# LED.net
KiCad netlist of a schematic drawn in Altium Designer
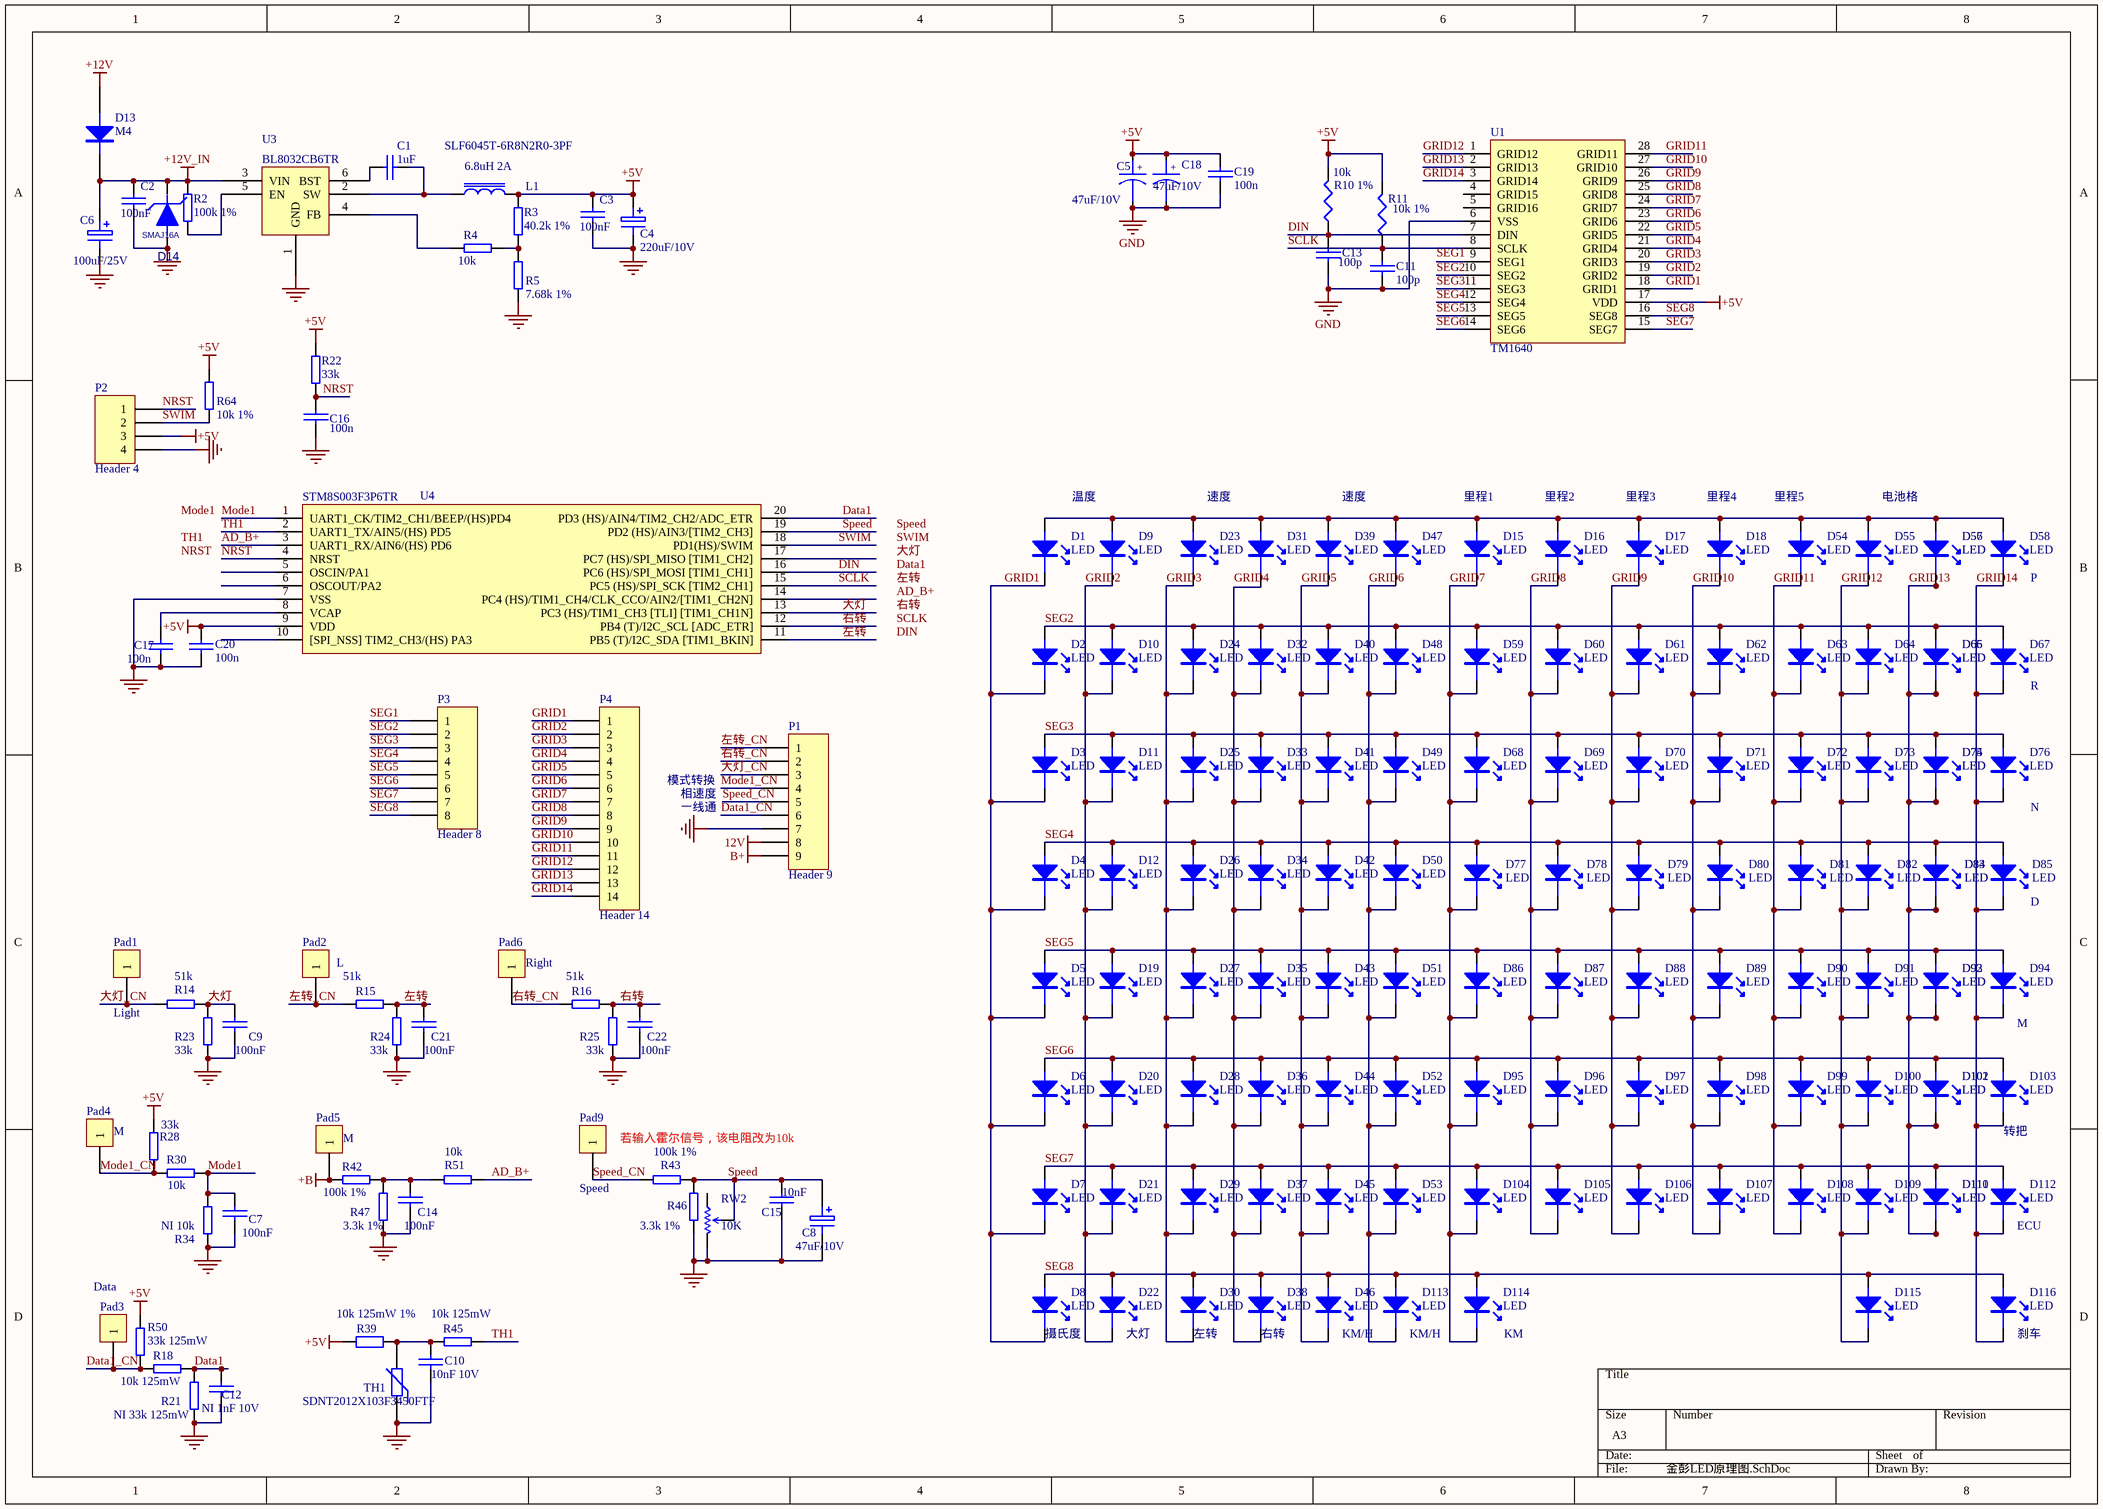
[diagram p0: 金彭LED原理图.SchDoc]

(export (version "E")
  (design (tool "Eeschema 10.0.6"))
  (components
    (comp (ref "C1") (value "1uF") (footprint "0805") (libsource (lib "whlSCHLIB") (part "WHLCAP")))
    (comp (ref "C2")
      (value "100nF")
      (footprint "0805")
      (description "Capacitor")
      (libsource (lib "*") (part "CAP"))
    )
    (comp (ref "C3")
      (value "100nF")
      (footprint "0805")
      (description "Capacitor")
      (libsource (lib "*") (part "CAP"))
    )
    (comp (ref "C4")
      (value "220uF/10V")
      (footprint "CE-D6.4")
      (description "Electrolytic Capacitor")
      (libsource (lib "*") (part "ELECTRO1"))
    )
    (comp (ref "C5") (value "47uF/10V") (footprint "CE-D5.2") (libsource (lib "dsp") (part "Capacitor")))
    (comp (ref "C6")
      (value "100uF/25V")
      (footprint "RB.2/.4")
      (description "Electrolytic Capacitor")
      (libsource (lib "*") (part "ELECTRO1"))
    )
    (comp (ref "C7")
      (value "100nF")
      (footprint "0805")
      (description "Capacitor")
      (libsource (lib "*") (part "CAP"))
    )
    (comp (ref "C8")
      (value "47uF/10V")
      (footprint "RB.1/.2")
      (description "Electrolytic Capacitor")
      (libsource (lib "") (part "ELECTRO1_1"))
    )
    (comp (ref "C9")
      (value "100nF")
      (footprint "0805")
      (description "Capacitor")
      (libsource (lib "*") (part "CAP"))
    )
    (comp (ref "C10")
      (value "10nF 10V")
      (footprint "0603")
      (description "Capacitor")
      (libsource (lib "*") (part "CAP"))
    )
    (comp (ref "C11") (value "100p") (footprint "0805") (libsource (lib "dsp") (part "Cap")))
    (comp (ref "C12")
      (value "NI 1nF 10V")
      (footprint "0603")
      (description "Capacitor")
      (libsource (lib "*") (part "CAP"))
    )
    (comp (ref "C13") (value "100p") (footprint "0805") (libsource (lib "dsp") (part "Cap")))
    (comp (ref "C14")
      (value "100nF")
      (footprint "0805")
      (description "Capacitor")
      (libsource (lib "*") (part "CAP"))
    )
    (comp (ref "C15")
      (value "10nF")
      (footprint "0603")
      (description "Capacitor")
      (libsource (lib "*") (part "CAP"))
    )
    (comp (ref "C16") (value "100n") (footprint "0603") (libsource (lib "dsp") (part "Cap")))
    (comp (ref "C17")
      (value "100n")
      (footprint "0603")
      (description "Capacitor")
      (libsource (lib "*") (part "CAP"))
    )
    (comp (ref "C18") (value "47uF/10V") (footprint "CE-D5.2") (libsource (lib "dsp") (part "Capacitor")))
    (comp (ref "C19") (value "100n") (footprint "0603") (libsource (lib "dsp") (part "Cap")))
    (comp (ref "C20") (value "100n") (footprint "0603") (libsource (lib "dsp") (part "Cap")))
    (comp (ref "C21")
      (value "100nF")
      (footprint "0805")
      (description "Capacitor")
      (libsource (lib "*") (part "CAP"))
    )
    (comp (ref "C22")
      (value "100nF")
      (footprint "0805")
      (description "Capacitor")
      (libsource (lib "*") (part "CAP"))
    )
    (comp (ref "D1") (value "LED") (footprint "0603") (libsource (lib "dsp") (part "LED")))
    (comp (ref "D2") (value "LED") (footprint "0603") (libsource (lib "dsp") (part "LED")))
    (comp (ref "D3") (value "LED") (footprint "0603") (libsource (lib "dsp") (part "LED")))
    (comp (ref "D4") (value "LED") (footprint "0603") (libsource (lib "dsp") (part "LED")))
    (comp (ref "D5") (value "LED") (footprint "0603") (libsource (lib "dsp") (part "LED")))
    (comp (ref "D6") (value "LED") (footprint "0603") (libsource (lib "dsp") (part "LED")))
    (comp (ref "D7") (value "LED") (footprint "0603") (libsource (lib "dsp") (part "LED")))
    (comp (ref "D8") (value "LED") (footprint "0603") (libsource (lib "dsp") (part "LED")))
    (comp (ref "D9") (value "LED") (footprint "0603") (libsource (lib "dsp") (part "LED")))
    (comp (ref "D10") (value "LED") (footprint "0603") (libsource (lib "dsp") (part "LED")))
    (comp (ref "D11") (value "LED") (footprint "0603") (libsource (lib "dsp") (part "LED")))
    (comp (ref "D12") (value "LED") (footprint "0603") (libsource (lib "dsp") (part "LED")))
    (comp (ref "D13")
      (value "M4")
      (footprint "SMA")
      (description "Diode")
      (libsource (lib "*") (part "DIODE"))
    )
    (comp (ref "D14")
      (value "SMAJ16A")
      (footprint "SMA")
      (description "5.1V,500mW,323")
      (libsource (lib "*") (part "DO-214AC_SMAJ"))
    )
    (comp (ref "D15") (value "LED") (footprint "0603") (libsource (lib "dsp") (part "LED")))
    (comp (ref "D16") (value "LED") (footprint "0603") (libsource (lib "dsp") (part "LED")))
    (comp (ref "D17") (value "LED") (footprint "0603") (libsource (lib "dsp") (part "LED")))
    (comp (ref "D18") (value "LED") (footprint "0603") (libsource (lib "dsp") (part "LED")))
    (comp (ref "D19") (value "LED") (footprint "0603") (libsource (lib "dsp") (part "LED")))
    (comp (ref "D20") (value "LED") (footprint "0603") (libsource (lib "dsp") (part "LED")))
    (comp (ref "D21") (value "LED") (footprint "0603") (libsource (lib "dsp") (part "LED")))
    (comp (ref "D22") (value "LED") (footprint "0603") (libsource (lib "dsp") (part "LED")))
    (comp (ref "D23") (value "LED") (footprint "0603") (libsource (lib "dsp") (part "LED")))
    (comp (ref "D24") (value "LED") (footprint "0603") (libsource (lib "dsp") (part "LED")))
    (comp (ref "D25") (value "LED") (footprint "0603") (libsource (lib "dsp") (part "LED")))
    (comp (ref "D26") (value "LED") (footprint "0603") (libsource (lib "dsp") (part "LED")))
    (comp (ref "D27") (value "LED") (footprint "0603") (libsource (lib "dsp") (part "LED")))
    (comp (ref "D28") (value "LED") (footprint "0603") (libsource (lib "dsp") (part "LED")))
    (comp (ref "D29") (value "LED") (footprint "0603") (libsource (lib "dsp") (part "LED")))
    (comp (ref "D30") (value "LED") (footprint "0603") (libsource (lib "dsp") (part "LED")))
    (comp (ref "D31") (value "LED") (footprint "0603") (libsource (lib "dsp") (part "LED")))
    (comp (ref "D32") (value "LED") (footprint "0603") (libsource (lib "dsp") (part "LED")))
    (comp (ref "D33") (value "LED") (footprint "0603") (libsource (lib "dsp") (part "LED")))
    (comp (ref "D34") (value "LED") (footprint "0603") (libsource (lib "dsp") (part "LED")))
    (comp (ref "D35") (value "LED") (footprint "0603") (libsource (lib "dsp") (part "LED")))
    (comp (ref "D36") (value "LED") (footprint "0603") (libsource (lib "dsp") (part "LED")))
    (comp (ref "D37") (value "LED") (footprint "0603") (libsource (lib "dsp") (part "LED")))
    (comp (ref "D38") (value "LED") (footprint "0603") (libsource (lib "dsp") (part "LED")))
    (comp (ref "D39") (value "LED") (footprint "0603") (libsource (lib "dsp") (part "LED")))
    (comp (ref "D40") (value "LED") (footprint "0603") (libsource (lib "dsp") (part "LED")))
    (comp (ref "D41") (value "LED") (footprint "0603") (libsource (lib "dsp") (part "LED")))
    (comp (ref "D42") (value "LED") (footprint "0603") (libsource (lib "dsp") (part "LED")))
    (comp (ref "D43") (value "LED") (footprint "0603") (libsource (lib "dsp") (part "LED")))
    (comp (ref "D44") (value "LED") (footprint "0603") (libsource (lib "dsp") (part "LED")))
    (comp (ref "D45") (value "LED") (footprint "0603") (libsource (lib "dsp") (part "LED")))
    (comp (ref "D46") (value "LED") (footprint "0603") (libsource (lib "dsp") (part "LED")))
    (comp (ref "D47") (value "LED") (footprint "0603") (libsource (lib "dsp") (part "LED")))
    (comp (ref "D48") (value "LED") (footprint "0603") (libsource (lib "dsp") (part "LED")))
    (comp (ref "D49") (value "LED") (footprint "0603") (libsource (lib "dsp") (part "LED")))
    (comp (ref "D50") (value "LED") (footprint "0603") (libsource (lib "dsp") (part "LED")))
    (comp (ref "D51") (value "LED") (footprint "0603") (libsource (lib "dsp") (part "LED")))
    (comp (ref "D52") (value "LED") (footprint "0603") (libsource (lib "dsp") (part "LED")))
    (comp (ref "D53") (value "LED") (footprint "0603") (libsource (lib "dsp") (part "LED")))
    (comp (ref "D54") (value "LED") (footprint "0603") (libsource (lib "dsp") (part "LED")))
    (comp (ref "D55") (value "LED") (footprint "0603") (libsource (lib "dsp") (part "LED")))
    (comp (ref "D56") (value "LED") (footprint "0603") (libsource (lib "dsp") (part "LED")))
    (comp (ref "D57") (value "LED") (footprint "0603") (libsource (lib "dsp") (part "LED")))
    (comp (ref "D58") (value "LED") (footprint "0603") (libsource (lib "dsp") (part "LED")))
    (comp (ref "D59") (value "LED") (footprint "0603") (libsource (lib "dsp") (part "LED")))
    (comp (ref "D60") (value "LED") (footprint "0603") (libsource (lib "dsp") (part "LED")))
    (comp (ref "D61") (value "LED") (footprint "0603") (libsource (lib "dsp") (part "LED")))
    (comp (ref "D62") (value "LED") (footprint "0603") (libsource (lib "dsp") (part "LED")))
    (comp (ref "D63") (value "LED") (footprint "0603") (libsource (lib "dsp") (part "LED")))
    (comp (ref "D64") (value "LED") (footprint "0603") (libsource (lib "dsp") (part "LED")))
    (comp (ref "D65") (value "LED") (footprint "0603") (libsource (lib "dsp") (part "LED")))
    (comp (ref "D66") (value "LED") (footprint "0603") (libsource (lib "dsp") (part "LED")))
    (comp (ref "D67") (value "LED") (footprint "0603") (libsource (lib "dsp") (part "LED")))
    (comp (ref "D68") (value "LED") (footprint "0603") (libsource (lib "dsp") (part "LED")))
    (comp (ref "D69") (value "LED") (footprint "0603") (libsource (lib "dsp") (part "LED")))
    (comp (ref "D70") (value "LED") (footprint "0603") (libsource (lib "dsp") (part "LED")))
    (comp (ref "D71") (value "LED") (footprint "0603") (libsource (lib "dsp") (part "LED")))
    (comp (ref "D72") (value "LED") (footprint "0603") (libsource (lib "dsp") (part "LED")))
    (comp (ref "D73") (value "LED") (footprint "0603") (libsource (lib "dsp") (part "LED")))
    (comp (ref "D74") (value "LED") (footprint "0603") (libsource (lib "dsp") (part "LED")))
    (comp (ref "D75") (value "LED") (footprint "0603") (libsource (lib "dsp") (part "LED")))
    (comp (ref "D76") (value "LED") (footprint "0603") (libsource (lib "dsp") (part "LED")))
    (comp (ref "D77") (value "LED") (footprint "0603") (libsource (lib "dsp") (part "LED")))
    (comp (ref "D78") (value "LED") (footprint "0603") (libsource (lib "dsp") (part "LED")))
    (comp (ref "D79") (value "LED") (footprint "0603") (libsource (lib "dsp") (part "LED")))
    (comp (ref "D80") (value "LED") (footprint "0603") (libsource (lib "dsp") (part "LED")))
    (comp (ref "D81") (value "LED") (footprint "0603") (libsource (lib "dsp") (part "LED")))
    (comp (ref "D82") (value "LED") (footprint "0603") (libsource (lib "dsp") (part "LED")))
    (comp (ref "D83") (value "LED") (footprint "0603") (libsource (lib "dsp") (part "LED")))
    (comp (ref "D84") (value "LED") (footprint "0603") (libsource (lib "dsp") (part "LED")))
    (comp (ref "D85") (value "LED") (footprint "0603") (libsource (lib "dsp") (part "LED")))
    (comp (ref "D86") (value "LED") (footprint "0603") (libsource (lib "dsp") (part "LED")))
    (comp (ref "D87") (value "LED") (footprint "0603") (libsource (lib "dsp") (part "LED")))
    (comp (ref "D88") (value "LED") (footprint "0603") (libsource (lib "dsp") (part "LED")))
    (comp (ref "D89") (value "LED") (footprint "0603") (libsource (lib "dsp") (part "LED")))
    (comp (ref "D90") (value "LED") (footprint "0603") (libsource (lib "dsp") (part "LED")))
    (comp (ref "D91") (value "LED") (footprint "0603") (libsource (lib "dsp") (part "LED")))
    (comp (ref "D92") (value "LED") (footprint "0603") (libsource (lib "dsp") (part "LED")))
    (comp (ref "D93") (value "LED") (footprint "0603") (libsource (lib "dsp") (part "LED")))
    (comp (ref "D94") (value "LED") (footprint "0603") (libsource (lib "dsp") (part "LED")))
    (comp (ref "D95") (value "LED") (footprint "0603") (libsource (lib "dsp") (part "LED")))
    (comp (ref "D96") (value "LED") (footprint "0603") (libsource (lib "dsp") (part "LED")))
    (comp (ref "D97") (value "LED") (footprint "0603") (libsource (lib "dsp") (part "LED")))
    (comp (ref "D98") (value "LED") (footprint "0603") (libsource (lib "dsp") (part "LED")))
    (comp (ref "D99") (value "LED") (footprint "0603") (libsource (lib "dsp") (part "LED")))
    (comp (ref "D100") (value "LED") (footprint "0603") (libsource (lib "dsp") (part "LED")))
    (comp (ref "D101") (value "LED") (footprint "0603") (libsource (lib "dsp") (part "LED")))
    (comp (ref "D102") (value "LED") (footprint "0603") (libsource (lib "dsp") (part "LED")))
    (comp (ref "D103") (value "LED") (footprint "0603") (libsource (lib "dsp") (part "LED")))
    (comp (ref "D104") (value "LED") (footprint "0603") (libsource (lib "dsp") (part "LED")))
    (comp (ref "D105") (value "LED") (footprint "0603") (libsource (lib "dsp") (part "LED")))
    (comp (ref "D106") (value "LED") (footprint "0603") (libsource (lib "dsp") (part "LED")))
    (comp (ref "D107") (value "LED") (footprint "0603") (libsource (lib "dsp") (part "LED")))
    (comp (ref "D108") (value "LED") (footprint "0603") (libsource (lib "dsp") (part "LED")))
    (comp (ref "D109") (value "LED") (footprint "0603") (libsource (lib "dsp") (part "LED")))
    (comp (ref "D110") (value "LED") (footprint "0603") (libsource (lib "dsp") (part "LED")))
    (comp (ref "D111") (value "LED") (footprint "0603") (libsource (lib "dsp") (part "LED")))
    (comp (ref "D112") (value "LED") (footprint "0603") (libsource (lib "dsp") (part "LED")))
    (comp (ref "D113") (value "LED") (footprint "0603") (libsource (lib "dsp") (part "LED")))
    (comp (ref "D114") (value "LED") (footprint "0603") (libsource (lib "dsp") (part "LED")))
    (comp (ref "D115") (value "LED") (footprint "0603") (libsource (lib "dsp") (part "LED")))
    (comp (ref "D116") (value "LED") (footprint "0603") (libsource (lib "dsp") (part "LED")))
    (comp (ref "L1")
      (value "SLF6045T-6R8N2R0-3PF")
      (footprint "L6025")
      (fields (field (name "ALTIUM_UNNAMED_1") "6.8uH 2A"))
      (libsource (lib "whlSCHLIB") (part "WHLL"))
    )
    (comp (ref "P1")
      (value "Header 9")
      (footprint "SIP9")
      (description "Header, 9-Pin")
      (fields (field (name "PUBLISHER") "Altium Limited"))
      (libsource (lib "dsp") (part "Header 9"))
    )
    (comp (ref "P2")
      (value "Header 4")
      (footprint "HDR1X4")
      (description "Header, 4-Pin")
      (fields (field (name "PUBLISHER") "Altium Limited"))
      (libsource (lib "Miscellaneous Connectors") (part "Header 4"))
    )
    (comp (ref "P3")
      (value "Header 8")
      (footprint "HDR1X8")
      (description "Header, 8-Pin")
      (fields (field (name "PUBLISHER") "Altium Limited"))
      (libsource (lib "Miscellaneous Connectors") (part "Header 8"))
    )
    (comp (ref "P4")
      (value "Header 14")
      (footprint "HDR1X14")
      (description "Header, 14-Pin")
      (fields (field (name "PUBLISHER") "Altium Limited"))
      (libsource (lib "9040") (part "Header 14"))
    )
    (comp (ref "Pad1")
      (value "Light")
      (footprint "PAD")
      (description "Connector")
      (libsource (lib "*") (part "CON1"))
    )
    (comp (ref "Pad2")
      (value "L")
      (footprint "PAD")
      (description "Connector")
      (libsource (lib "*") (part "CON1"))
    )
    (comp (ref "Pad3")
      (value "Data")
      (footprint "PAD")
      (description "Connector")
      (libsource (lib "*") (part "CON1"))
    )
    (comp (ref "Pad4")
      (value "M")
      (footprint "PAD")
      (description "Connector")
      (libsource (lib "*") (part "CON1"))
    )
    (comp (ref "Pad5")
      (value "M")
      (footprint "PAD")
      (description "Connector")
      (libsource (lib "*") (part "CON1"))
    )
    (comp (ref "Pad6")
      (value "Right")
      (footprint "PAD")
      (description "Connector")
      (libsource (lib "*") (part "CON1"))
    )
    (comp (ref "Pad9")
      (value "Speed")
      (footprint "PAD")
      (description "Connector")
      (libsource (lib "*") (part "CON1"))
    )
    (comp (ref "R2") (value "100k 1%") (footprint "0805") (libsource (lib "whlSCHLIB") (part "WHLRES")))
    (comp (ref "R3") (value "40.2k 1%") (footprint "0805") (libsource (lib "whlSCHLIB") (part "WHLRES")))
    (comp (ref "R4") (value "10k") (footprint "0603") (libsource (lib "whlSCHLIB") (part "WHLRES")))
    (comp (ref "R5") (value "7.68k 1%") (footprint "0603") (libsource (lib "whlSCHLIB") (part "WHLRES")))
    (comp (ref "R10 1%") (value "10k") (footprint "0805") (libsource (lib "dsp") (part "RES1")))
    (comp (ref "R11") (value "10k 1%") (footprint "0805") (libsource (lib "dsp") (part "RES1")))
    (comp (ref "R14") (value "51k") (footprint "0805") (libsource (lib "whlSCHLIB") (part "WHLRES")))
    (comp (ref "R15") (value "51k") (footprint "0805") (libsource (lib "whlSCHLIB") (part "WHLRES")))
    (comp (ref "R16") (value "51k") (footprint "0805") (libsource (lib "whlSCHLIB") (part "WHLRES")))
    (comp (ref "R18") (value "10k 125mW") (footprint "0805") (libsource (lib "whlSCHLIB") (part "WHLRES")))
    (comp (ref "R21") (value "NI 33k 125mW") (footprint "0805") (libsource (lib "whlSCHLIB") (part "WHLRES")))
    (comp (ref "R22")
      (value "33k")
      (footprint "0805")
      (fields (field (name "POWER") "125mW"))
      (libsource (lib "whlSCHLIB") (part "WHLRES"))
    )
    (comp (ref "R23") (value "33k") (footprint "0805") (libsource (lib "whlSCHLIB") (part "WHLRES")))
    (comp (ref "R24") (value "33k") (footprint "0805") (libsource (lib "whlSCHLIB") (part "WHLRES")))
    (comp (ref "R25") (value "33k") (footprint "0805") (libsource (lib "whlSCHLIB") (part "WHLRES")))
    (comp (ref "R28") (value "33k") (footprint "0805") (libsource (lib "whlSCHLIB") (part "WHLRES")))
    (comp (ref "R30") (value "10k") (footprint "0805") (libsource (lib "whlSCHLIB") (part "WHLRES")))
    (comp (ref "R34") (value "NI 10k") (footprint "0805") (libsource (lib "whlSCHLIB") (part "WHLRES")))
    (comp (ref "R39")
      (value "10k 125mW 1%")
      (footprint "0805")
      (description "Resistor")
      (fields (field (name "PUBLISHER") "Altium Limited"))
      (libsource (lib "*") (part "Res2"))
    )
    (comp (ref "R42") (value "100k 1%") (footprint "0805") (libsource (lib "whlSCHLIB") (part "WHLRES")))
    (comp (ref "R43") (value "100k 1%") (footprint "0805") (libsource (lib "whlSCHLIB") (part "WHLRES")))
    (comp (ref "R45") (value "10k 125mW") (footprint "0805") (libsource (lib "whlSCHLIB") (part "WHLRES")))
    (comp (ref "R46") (value "3.3k 1%") (footprint "0805") (libsource (lib "whlSCHLIB") (part "WHLRES")))
    (comp (ref "R47") (value "3.3k 1%") (footprint "0805") (libsource (lib "whlSCHLIB") (part "WHLRES")))
    (comp (ref "R50") (value "33k 125mW") (footprint "0805") (libsource (lib "whlSCHLIB") (part "WHLRES")))
    (comp (ref "R51") (value "10k") (footprint "0805") (libsource (lib "whlSCHLIB") (part "WHLRES")))
    (comp (ref "R64") (value "10k 1%") (footprint "0805") (libsource (lib "whlSCHLIB") (part "WHLRES")))
    (comp (ref "RW2") (value "10K") (footprint "RW-3*3SMD") (libsource (lib "*") (part "RW1")))
    (comp (ref "TH1")
      (value "SDNT2012X103F3450FTF")
      (footprint "0805")
      (description "Varistor (Voltage-Sensitive Resistor)")
      (fields (field (name "PUBLISHER") "Altium Limited"))
      (libsource (lib "Miscellaneous Devices") (part "Res Varistor"))
    )
    (comp (ref "U1") (value "TM1640") (footprint "SOP28") (libsource (lib "9040") (part "TM1640")))
    (comp (ref "U3")
      (value "BL8032CB6TR")
      (footprint "SOT23-6-BL")
      (libsource (lib "SchMylib1") (part "BL8032"))
    )
    (comp (ref "U4")
      (value "STM8S003F3P6TR")
      (footprint "SSOP20")
      (libsource (lib "音效器") (part "STM8S003F3P6"))
    )
  )
  (nets
    (net (code "1") (name "+5V") (class "Default")
      (node (ref "C18") (pin "1") (pinfunction "1_1") (pintype "passive"))
      (node (ref "C19") (pin "2") (pinfunction "2_2") (pintype "passive"))
      (node (ref "C20") (pin "2") (pinfunction "2_2") (pintype "passive"))
      (node (ref "C3") (pin "1") (pinfunction "1_1") (pintype "passive"))
      (node (ref "C4") (pin "1") (pinfunction "1_1") (pintype "passive"))
      (node (ref "C5") (pin "1") (pinfunction "1_1") (pintype "passive"))
      (node (ref "L1") (pin "2") (pinfunction "2_2") (pintype "passive"))
      (node (ref "P2") (pin "3") (pinfunction "3_3") (pintype "passive"))
      (node (ref "R10 1%") (pin "2") (pinfunction "2_2") (pintype "passive"))
      (node (ref "R11") (pin "2") (pinfunction "2_2") (pintype "passive"))
      (node (ref "R22") (pin "2") (pinfunction "2_2") (pintype "passive"))
      (node (ref "R28") (pin "1") (pinfunction "1_1") (pintype "passive"))
      (node (ref "R3") (pin "1") (pinfunction "1_1") (pintype "passive"))
      (node (ref "R39") (pin "2") (pinfunction "2_2") (pintype "passive"))
      (node (ref "R50") (pin "1") (pinfunction "1_1") (pintype "passive"))
      (node (ref "R64") (pin "1") (pinfunction "1_1") (pintype "passive"))
      (node (ref "U1") (pin "17") (pinfunction "VDD_17") (pintype "passive"))
      (node (ref "U4") (pin "9") (pinfunction "VDD_9") (pintype "passive"))
    )
    (net (code "2") (name "+12V") (class "Default")
      (node (ref "D13") (pin "1") (pinfunction "A_1") (pintype "passive"))
    )
    (net (code "3") (name "+12V_IN") (class "Default")
      (node (ref "C2") (pin "1") (pinfunction "1_1") (pintype "passive"))
      (node (ref "C6") (pin "1") (pinfunction "1_1") (pintype "passive"))
      (node (ref "D13") (pin "2") (pinfunction "K_2") (pintype "passive"))
      (node (ref "D14") (pin "2") (pinfunction "2_2") (pintype "passive"))
      (node (ref "R2") (pin "1") (pinfunction "1_1") (pintype "passive"))
      (node (ref "U3") (pin "3") (pinfunction "VIN_3") (pintype "passive"))
    )
    (net (code "4") (name "+B") (class "Default")
      (node (ref "Pad5") (pin "1") (pinfunction "1_1") (pintype "passive"))
      (node (ref "R42") (pin "2") (pinfunction "2_2") (pintype "passive"))
    )
    (net (code "5") (name "/AD_B+") (class "Default")
      (node (ref "R51") (pin "1") (pinfunction "1_1") (pintype "passive"))
      (node (ref "U4") (pin "3") (pinfunction "UART1_RX/AIN6/(HS)_PD6_3") (pintype "passive"))
    )
    (net (code "6") (name "/DIN") (class "Default")
      (node (ref "C13") (pin "2") (pinfunction "2_2") (pintype "passive"))
      (node (ref "R10 1%") (pin "1") (pinfunction "1_1") (pintype "passive"))
      (node (ref "U1") (pin "7") (pinfunction "DIN_7") (pintype "passive"))
      (node (ref "U4") (pin "16") (pinfunction "PC6_(HS)/SPI_MOSI_[TIM1_CH1]_16") (pintype "passive"))
    )
    (net (code "7") (name "/Data1") (class "Default")
      (node (ref "C12") (pin "1") (pinfunction "1_1") (pintype "passive"))
      (node (ref "R18") (pin "1") (pinfunction "1_1") (pintype "passive"))
      (node (ref "R21") (pin "1") (pinfunction "1_1") (pintype "passive"))
      (node (ref "U4") (pin "20") (pinfunction "PD3_(HS)/AIN4/TIM2_CH2/ADC_ETR_20") (pintype "passive"))
    )
    (net (code "8") (name "/Data1_CN") (class "Default")
      (node (ref "P1") (pin "6") (pinfunction "6_6") (pintype "passive"))
      (node (ref "Pad3") (pin "1") (pinfunction "1_1") (pintype "passive"))
      (node (ref "R18") (pin "2") (pinfunction "2_2") (pintype "passive"))
      (node (ref "R50") (pin "2") (pinfunction "2_2") (pintype "passive"))
    )
    (net (code "9") (name "/GRID1") (class "Default")
      (node (ref "D1") (pin "2") (pinfunction "2_2") (pintype "passive"))
      (node (ref "D2") (pin "2") (pinfunction "2_2") (pintype "passive"))
      (node (ref "D3") (pin "2") (pinfunction "2_2") (pintype "passive"))
      (node (ref "D4") (pin "2") (pinfunction "2_2") (pintype "passive"))
      (node (ref "D5") (pin "2") (pinfunction "2_2") (pintype "passive"))
      (node (ref "D6") (pin "2") (pinfunction "2_2") (pintype "passive"))
      (node (ref "D7") (pin "2") (pinfunction "2_2") (pintype "passive"))
      (node (ref "D8") (pin "2") (pinfunction "2_2") (pintype "passive"))
      (node (ref "P4") (pin "1") (pinfunction "1_1") (pintype "passive"))
      (node (ref "U1") (pin "18") (pinfunction "GRID1_18") (pintype "passive"))
    )
    (net (code "10") (name "/GRID2") (class "Default")
      (node (ref "D10") (pin "2") (pinfunction "2_2") (pintype "passive"))
      (node (ref "D11") (pin "2") (pinfunction "2_2") (pintype "passive"))
      (node (ref "D12") (pin "2") (pinfunction "2_2") (pintype "passive"))
      (node (ref "D19") (pin "2") (pinfunction "2_2") (pintype "passive"))
      (node (ref "D20") (pin "2") (pinfunction "2_2") (pintype "passive"))
      (node (ref "D21") (pin "2") (pinfunction "2_2") (pintype "passive"))
      (node (ref "D22") (pin "2") (pinfunction "2_2") (pintype "passive"))
      (node (ref "D9") (pin "2") (pinfunction "2_2") (pintype "passive"))
      (node (ref "P4") (pin "2") (pinfunction "2_2") (pintype "passive"))
      (node (ref "U1") (pin "19") (pinfunction "GRID2_19") (pintype "passive"))
    )
    (net (code "11") (name "/GRID3") (class "Default")
      (node (ref "D23") (pin "2") (pinfunction "2_2") (pintype "passive"))
      (node (ref "D24") (pin "2") (pinfunction "2_2") (pintype "passive"))
      (node (ref "D25") (pin "2") (pinfunction "2_2") (pintype "passive"))
      (node (ref "D26") (pin "2") (pinfunction "2_2") (pintype "passive"))
      (node (ref "D27") (pin "2") (pinfunction "2_2") (pintype "passive"))
      (node (ref "D28") (pin "2") (pinfunction "2_2") (pintype "passive"))
      (node (ref "D29") (pin "2") (pinfunction "2_2") (pintype "passive"))
      (node (ref "D30") (pin "2") (pinfunction "2_2") (pintype "passive"))
      (node (ref "P4") (pin "3") (pinfunction "3_3") (pintype "passive"))
      (node (ref "U1") (pin "20") (pinfunction "GRID3_20") (pintype "passive"))
    )
    (net (code "12") (name "/GRID4") (class "Default")
      (node (ref "P4") (pin "4") (pinfunction "4_4") (pintype "passive"))
      (node (ref "U1") (pin "21") (pinfunction "GRID4_21") (pintype "passive"))
    )
    (net (code "13") (name "/GRID5") (class "Default")
      (node (ref "D39") (pin "2") (pinfunction "2_2") (pintype "passive"))
      (node (ref "D40") (pin "2") (pinfunction "2_2") (pintype "passive"))
      (node (ref "D41") (pin "2") (pinfunction "2_2") (pintype "passive"))
      (node (ref "D42") (pin "2") (pinfunction "2_2") (pintype "passive"))
      (node (ref "D43") (pin "2") (pinfunction "2_2") (pintype "passive"))
      (node (ref "D44") (pin "2") (pinfunction "2_2") (pintype "passive"))
      (node (ref "D45") (pin "2") (pinfunction "2_2") (pintype "passive"))
      (node (ref "D46") (pin "2") (pinfunction "2_2") (pintype "passive"))
      (node (ref "P4") (pin "5") (pinfunction "5_5") (pintype "passive"))
      (node (ref "U1") (pin "22") (pinfunction "GRID5_22") (pintype "passive"))
    )
    (net (code "14") (name "/GRID6") (class "Default")
      (node (ref "D113") (pin "2") (pinfunction "2_2") (pintype "passive"))
      (node (ref "D47") (pin "2") (pinfunction "2_2") (pintype "passive"))
      (node (ref "D48") (pin "2") (pinfunction "2_2") (pintype "passive"))
      (node (ref "D49") (pin "2") (pinfunction "2_2") (pintype "passive"))
      (node (ref "D50") (pin "2") (pinfunction "2_2") (pintype "passive"))
      (node (ref "D51") (pin "2") (pinfunction "2_2") (pintype "passive"))
      (node (ref "D52") (pin "2") (pinfunction "2_2") (pintype "passive"))
      (node (ref "D53") (pin "2") (pinfunction "2_2") (pintype "passive"))
      (node (ref "P4") (pin "6") (pinfunction "6_6") (pintype "passive"))
      (node (ref "U1") (pin "23") (pinfunction "GRID6_23") (pintype "passive"))
    )
    (net (code "15") (name "/GRID7") (class "Default")
      (node (ref "D104") (pin "2") (pinfunction "2_2") (pintype "passive"))
      (node (ref "D114") (pin "2") (pinfunction "2_2") (pintype "passive"))
      (node (ref "D15") (pin "2") (pinfunction "2_2") (pintype "passive"))
      (node (ref "D59") (pin "2") (pinfunction "2_2") (pintype "passive"))
      (node (ref "D68") (pin "2") (pinfunction "2_2") (pintype "passive"))
      (node (ref "D77") (pin "2") (pinfunction "2_2") (pintype "passive"))
      (node (ref "D86") (pin "2") (pinfunction "2_2") (pintype "passive"))
      (node (ref "D95") (pin "2") (pinfunction "2_2") (pintype "passive"))
      (node (ref "P4") (pin "7") (pinfunction "7_7") (pintype "passive"))
      (node (ref "U1") (pin "24") (pinfunction "GRID7_24") (pintype "passive"))
    )
    (net (code "16") (name "/GRID8") (class "Default")
      (node (ref "D105") (pin "2") (pinfunction "2_2") (pintype "passive"))
      (node (ref "D16") (pin "2") (pinfunction "2_2") (pintype "passive"))
      (node (ref "D60") (pin "2") (pinfunction "2_2") (pintype "passive"))
      (node (ref "D69") (pin "2") (pinfunction "2_2") (pintype "passive"))
      (node (ref "D78") (pin "2") (pinfunction "2_2") (pintype "passive"))
      (node (ref "D87") (pin "2") (pinfunction "2_2") (pintype "passive"))
      (node (ref "D96") (pin "2") (pinfunction "2_2") (pintype "passive"))
      (node (ref "P4") (pin "8") (pinfunction "8_8") (pintype "passive"))
      (node (ref "U1") (pin "25") (pinfunction "GRID8_25") (pintype "passive"))
    )
    (net (code "17") (name "/GRID9") (class "Default")
      (node (ref "D106") (pin "2") (pinfunction "2_2") (pintype "passive"))
      (node (ref "D17") (pin "2") (pinfunction "2_2") (pintype "passive"))
      (node (ref "D61") (pin "2") (pinfunction "2_2") (pintype "passive"))
      (node (ref "D70") (pin "2") (pinfunction "2_2") (pintype "passive"))
      (node (ref "D79") (pin "2") (pinfunction "2_2") (pintype "passive"))
      (node (ref "D88") (pin "2") (pinfunction "2_2") (pintype "passive"))
      (node (ref "D97") (pin "2") (pinfunction "2_2") (pintype "passive"))
      (node (ref "P4") (pin "9") (pinfunction "9_9") (pintype "passive"))
      (node (ref "U1") (pin "26") (pinfunction "GRID9_26") (pintype "passive"))
    )
    (net (code "18") (name "/GRID10") (class "Default")
      (node (ref "D107") (pin "2") (pinfunction "2_2") (pintype "passive"))
      (node (ref "D18") (pin "2") (pinfunction "2_2") (pintype "passive"))
      (node (ref "D62") (pin "2") (pinfunction "2_2") (pintype "passive"))
      (node (ref "D71") (pin "2") (pinfunction "2_2") (pintype "passive"))
      (node (ref "D80") (pin "2") (pinfunction "2_2") (pintype "passive"))
      (node (ref "D89") (pin "2") (pinfunction "2_2") (pintype "passive"))
      (node (ref "D98") (pin "2") (pinfunction "2_2") (pintype "passive"))
      (node (ref "P4") (pin "10") (pinfunction "10_10") (pintype "passive"))
      (node (ref "U1") (pin "27") (pinfunction "GRID10_27") (pintype "passive"))
    )
    (net (code "19") (name "/GRID11") (class "Default")
      (node (ref "D108") (pin "2") (pinfunction "2_2") (pintype "passive"))
      (node (ref "D54") (pin "2") (pinfunction "2_2") (pintype "passive"))
      (node (ref "D63") (pin "2") (pinfunction "2_2") (pintype "passive"))
      (node (ref "D72") (pin "2") (pinfunction "2_2") (pintype "passive"))
      (node (ref "D81") (pin "2") (pinfunction "2_2") (pintype "passive"))
      (node (ref "D90") (pin "2") (pinfunction "2_2") (pintype "passive"))
      (node (ref "D99") (pin "2") (pinfunction "2_2") (pintype "passive"))
      (node (ref "P4") (pin "11") (pinfunction "11_11") (pintype "passive"))
      (node (ref "U1") (pin "28") (pinfunction "GRID11_28") (pintype "passive"))
    )
    (net (code "20") (name "/GRID12") (class "Default")
      (node (ref "D100") (pin "2") (pinfunction "2_2") (pintype "passive"))
      (node (ref "D109") (pin "2") (pinfunction "2_2") (pintype "passive"))
      (node (ref "D115") (pin "2") (pinfunction "2_2") (pintype "passive"))
      (node (ref "D55") (pin "2") (pinfunction "2_2") (pintype "passive"))
      (node (ref "D64") (pin "2") (pinfunction "2_2") (pintype "passive"))
      (node (ref "D73") (pin "2") (pinfunction "2_2") (pintype "passive"))
      (node (ref "D82") (pin "2") (pinfunction "2_2") (pintype "passive"))
      (node (ref "D91") (pin "2") (pinfunction "2_2") (pintype "passive"))
      (node (ref "P4") (pin "12") (pinfunction "12_12") (pintype "passive"))
      (node (ref "U1") (pin "1") (pinfunction "GRID12_1") (pintype "passive"))
    )
    (net (code "21") (name "/GRID13") (class "Default")
      (node (ref "D101") (pin "2") (pinfunction "2_2") (pintype "passive"))
      (node (ref "D102") (pin "2") (pinfunction "2_2") (pintype "passive"))
      (node (ref "D110") (pin "2") (pinfunction "2_2") (pintype "passive"))
      (node (ref "D111") (pin "2") (pinfunction "2_2") (pintype "passive"))
      (node (ref "D56") (pin "2") (pinfunction "2_2") (pintype "passive"))
      (node (ref "D57") (pin "2") (pinfunction "2_2") (pintype "passive"))
      (node (ref "D65") (pin "2") (pinfunction "2_2") (pintype "passive"))
      (node (ref "D66") (pin "2") (pinfunction "2_2") (pintype "passive"))
      (node (ref "D74") (pin "2") (pinfunction "2_2") (pintype "passive"))
      (node (ref "D75") (pin "2") (pinfunction "2_2") (pintype "passive"))
      (node (ref "D83") (pin "2") (pinfunction "2_2") (pintype "passive"))
      (node (ref "D84") (pin "2") (pinfunction "2_2") (pintype "passive"))
      (node (ref "D92") (pin "2") (pinfunction "2_2") (pintype "passive"))
      (node (ref "D93") (pin "2") (pinfunction "2_2") (pintype "passive"))
      (node (ref "P4") (pin "13") (pinfunction "13_13") (pintype "passive"))
      (node (ref "U1") (pin "2") (pinfunction "GRID13_2") (pintype "passive"))
    )
    (net (code "22") (name "/GRID14") (class "Default")
      (node (ref "D103") (pin "2") (pinfunction "2_2") (pintype "passive"))
      (node (ref "D112") (pin "2") (pinfunction "2_2") (pintype "passive"))
      (node (ref "D116") (pin "2") (pinfunction "2_2") (pintype "passive"))
      (node (ref "D58") (pin "2") (pinfunction "2_2") (pintype "passive"))
      (node (ref "D67") (pin "2") (pinfunction "2_2") (pintype "passive"))
      (node (ref "D76") (pin "2") (pinfunction "2_2") (pintype "passive"))
      (node (ref "D85") (pin "2") (pinfunction "2_2") (pintype "passive"))
      (node (ref "D94") (pin "2") (pinfunction "2_2") (pintype "passive"))
      (node (ref "P4") (pin "14") (pinfunction "14_14") (pintype "passive"))
      (node (ref "U1") (pin "3") (pinfunction "GRID14_3") (pintype "passive"))
    )
    (net (code "23") (name "/Mode1") (class "Default")
      (node (ref "C7") (pin "1") (pinfunction "1_1") (pintype "passive"))
      (node (ref "R30") (pin "1") (pinfunction "1_1") (pintype "passive"))
      (node (ref "R34") (pin "1") (pinfunction "1_1") (pintype "passive"))
      (node (ref "U4") (pin "1") (pinfunction "UART1_CK/TIM2_CH1/BEEP/(HS)PD4_1") (pintype "passive"))
    )
    (net (code "24") (name "/Mode1_CN") (class "Default")
      (node (ref "P1") (pin "4") (pinfunction "4_4") (pintype "passive"))
      (node (ref "Pad4") (pin "1") (pinfunction "1_1") (pintype "passive"))
      (node (ref "R28") (pin "2") (pinfunction "2_2") (pintype "passive"))
      (node (ref "R30") (pin "2") (pinfunction "2_2") (pintype "passive"))
    )
    (net (code "25") (name "/NRST") (class "Default")
      (node (ref "C16") (pin "2") (pinfunction "2_2") (pintype "passive"))
      (node (ref "P2") (pin "1") (pinfunction "1_1") (pintype "passive"))
      (node (ref "R22") (pin "1") (pinfunction "1_1") (pintype "passive"))
      (node (ref "U4") (pin "4") (pinfunction "NRST_4") (pintype "passive"))
    )
    (net (code "26") (name "/SCLK") (class "Default")
      (node (ref "C11") (pin "2") (pinfunction "2_2") (pintype "passive"))
      (node (ref "R11") (pin "1") (pinfunction "1_1") (pintype "passive"))
      (node (ref "U1") (pin "8") (pinfunction "SCLK_8") (pintype "passive"))
      (node (ref "U4") (pin "15") (pinfunction "PC5_(HS)/SPI_SCK_[TIM2_CH1]_15") (pintype "passive"))
    )
    (net (code "27") (name "/SEG1") (class "Default")
      (node (ref "P3") (pin "1") (pinfunction "1_1") (pintype "passive"))
    )
    (net (code "28") (name "/SEG2") (class "Default")
      (node (ref "D10") (pin "1") (pinfunction "1_1") (pintype "passive"))
      (node (ref "D2") (pin "1") (pinfunction "1_1") (pintype "passive"))
      (node (ref "D24") (pin "1") (pinfunction "1_1") (pintype "passive"))
      (node (ref "D32") (pin "1") (pinfunction "1_1") (pintype "passive"))
      (node (ref "D40") (pin "1") (pinfunction "1_1") (pintype "passive"))
      (node (ref "D48") (pin "1") (pinfunction "1_1") (pintype "passive"))
      (node (ref "D59") (pin "1") (pinfunction "1_1") (pintype "passive"))
      (node (ref "D60") (pin "1") (pinfunction "1_1") (pintype "passive"))
      (node (ref "D61") (pin "1") (pinfunction "1_1") (pintype "passive"))
      (node (ref "D62") (pin "1") (pinfunction "1_1") (pintype "passive"))
      (node (ref "D63") (pin "1") (pinfunction "1_1") (pintype "passive"))
      (node (ref "D64") (pin "1") (pinfunction "1_1") (pintype "passive"))
      (node (ref "D65") (pin "1") (pinfunction "1_1") (pintype "passive"))
      (node (ref "D66") (pin "1") (pinfunction "1_1") (pintype "passive"))
      (node (ref "D67") (pin "1") (pinfunction "1_1") (pintype "passive"))
      (node (ref "P3") (pin "2") (pinfunction "2_2") (pintype "passive"))
      (node (ref "U1") (pin "10") (pinfunction "SEG2_10") (pintype "passive"))
    )
    (net (code "29") (name "/SEG3") (class "Default")
      (node (ref "D11") (pin "1") (pinfunction "1_1") (pintype "passive"))
      (node (ref "D25") (pin "1") (pinfunction "1_1") (pintype "passive"))
      (node (ref "D3") (pin "1") (pinfunction "1_1") (pintype "passive"))
      (node (ref "D33") (pin "1") (pinfunction "1_1") (pintype "passive"))
      (node (ref "D41") (pin "1") (pinfunction "1_1") (pintype "passive"))
      (node (ref "D49") (pin "1") (pinfunction "1_1") (pintype "passive"))
      (node (ref "D68") (pin "1") (pinfunction "1_1") (pintype "passive"))
      (node (ref "D69") (pin "1") (pinfunction "1_1") (pintype "passive"))
      (node (ref "D70") (pin "1") (pinfunction "1_1") (pintype "passive"))
      (node (ref "D71") (pin "1") (pinfunction "1_1") (pintype "passive"))
      (node (ref "D72") (pin "1") (pinfunction "1_1") (pintype "passive"))
      (node (ref "D73") (pin "1") (pinfunction "1_1") (pintype "passive"))
      (node (ref "D74") (pin "1") (pinfunction "1_1") (pintype "passive"))
      (node (ref "D75") (pin "1") (pinfunction "1_1") (pintype "passive"))
      (node (ref "D76") (pin "1") (pinfunction "1_1") (pintype "passive"))
      (node (ref "P3") (pin "3") (pinfunction "3_3") (pintype "passive"))
      (node (ref "U1") (pin "11") (pinfunction "SEG3_11") (pintype "passive"))
    )
    (net (code "30") (name "/SEG4") (class "Default")
      (node (ref "D12") (pin "1") (pinfunction "1_1") (pintype "passive"))
      (node (ref "D26") (pin "1") (pinfunction "1_1") (pintype "passive"))
      (node (ref "D34") (pin "1") (pinfunction "1_1") (pintype "passive"))
      (node (ref "D4") (pin "1") (pinfunction "1_1") (pintype "passive"))
      (node (ref "D42") (pin "1") (pinfunction "1_1") (pintype "passive"))
      (node (ref "D50") (pin "1") (pinfunction "1_1") (pintype "passive"))
      (node (ref "D77") (pin "1") (pinfunction "1_1") (pintype "passive"))
      (node (ref "D78") (pin "1") (pinfunction "1_1") (pintype "passive"))
      (node (ref "D79") (pin "1") (pinfunction "1_1") (pintype "passive"))
      (node (ref "D80") (pin "1") (pinfunction "1_1") (pintype "passive"))
      (node (ref "D81") (pin "1") (pinfunction "1_1") (pintype "passive"))
      (node (ref "D82") (pin "1") (pinfunction "1_1") (pintype "passive"))
      (node (ref "D83") (pin "1") (pinfunction "1_1") (pintype "passive"))
      (node (ref "D84") (pin "1") (pinfunction "1_1") (pintype "passive"))
      (node (ref "D85") (pin "1") (pinfunction "1_1") (pintype "passive"))
      (node (ref "P3") (pin "4") (pinfunction "4_4") (pintype "passive"))
      (node (ref "U1") (pin "12") (pinfunction "SEG4_12") (pintype "passive"))
    )
    (net (code "31") (name "/SEG5") (class "Default")
      (node (ref "D19") (pin "1") (pinfunction "1_1") (pintype "passive"))
      (node (ref "D27") (pin "1") (pinfunction "1_1") (pintype "passive"))
      (node (ref "D35") (pin "1") (pinfunction "1_1") (pintype "passive"))
      (node (ref "D43") (pin "1") (pinfunction "1_1") (pintype "passive"))
      (node (ref "D5") (pin "1") (pinfunction "1_1") (pintype "passive"))
      (node (ref "D51") (pin "1") (pinfunction "1_1") (pintype "passive"))
      (node (ref "D86") (pin "1") (pinfunction "1_1") (pintype "passive"))
      (node (ref "D87") (pin "1") (pinfunction "1_1") (pintype "passive"))
      (node (ref "D88") (pin "1") (pinfunction "1_1") (pintype "passive"))
      (node (ref "D89") (pin "1") (pinfunction "1_1") (pintype "passive"))
      (node (ref "D90") (pin "1") (pinfunction "1_1") (pintype "passive"))
      (node (ref "D91") (pin "1") (pinfunction "1_1") (pintype "passive"))
      (node (ref "D92") (pin "1") (pinfunction "1_1") (pintype "passive"))
      (node (ref "D93") (pin "1") (pinfunction "1_1") (pintype "passive"))
      (node (ref "D94") (pin "1") (pinfunction "1_1") (pintype "passive"))
      (node (ref "P3") (pin "5") (pinfunction "5_5") (pintype "passive"))
      (node (ref "U1") (pin "13") (pinfunction "SEG5_13") (pintype "passive"))
    )
    (net (code "32") (name "/SEG6") (class "Default")
      (node (ref "D100") (pin "1") (pinfunction "1_1") (pintype "passive"))
      (node (ref "D101") (pin "1") (pinfunction "1_1") (pintype "passive"))
      (node (ref "D102") (pin "1") (pinfunction "1_1") (pintype "passive"))
      (node (ref "D103") (pin "1") (pinfunction "1_1") (pintype "passive"))
      (node (ref "D20") (pin "1") (pinfunction "1_1") (pintype "passive"))
      (node (ref "D28") (pin "1") (pinfunction "1_1") (pintype "passive"))
      (node (ref "D36") (pin "1") (pinfunction "1_1") (pintype "passive"))
      (node (ref "D44") (pin "1") (pinfunction "1_1") (pintype "passive"))
      (node (ref "D52") (pin "1") (pinfunction "1_1") (pintype "passive"))
      (node (ref "D6") (pin "1") (pinfunction "1_1") (pintype "passive"))
      (node (ref "D95") (pin "1") (pinfunction "1_1") (pintype "passive"))
      (node (ref "D96") (pin "1") (pinfunction "1_1") (pintype "passive"))
      (node (ref "D97") (pin "1") (pinfunction "1_1") (pintype "passive"))
      (node (ref "D98") (pin "1") (pinfunction "1_1") (pintype "passive"))
      (node (ref "D99") (pin "1") (pinfunction "1_1") (pintype "passive"))
      (node (ref "P3") (pin "6") (pinfunction "6_6") (pintype "passive"))
      (node (ref "U1") (pin "14") (pinfunction "SEG6_14") (pintype "passive"))
    )
    (net (code "33") (name "/SEG7") (class "Default")
      (node (ref "D104") (pin "1") (pinfunction "1_1") (pintype "passive"))
      (node (ref "D105") (pin "1") (pinfunction "1_1") (pintype "passive"))
      (node (ref "D106") (pin "1") (pinfunction "1_1") (pintype "passive"))
      (node (ref "D107") (pin "1") (pinfunction "1_1") (pintype "passive"))
      (node (ref "D108") (pin "1") (pinfunction "1_1") (pintype "passive"))
      (node (ref "D109") (pin "1") (pinfunction "1_1") (pintype "passive"))
      (node (ref "D110") (pin "1") (pinfunction "1_1") (pintype "passive"))
      (node (ref "D111") (pin "1") (pinfunction "1_1") (pintype "passive"))
      (node (ref "D112") (pin "1") (pinfunction "1_1") (pintype "passive"))
      (node (ref "D21") (pin "1") (pinfunction "1_1") (pintype "passive"))
      (node (ref "D29") (pin "1") (pinfunction "1_1") (pintype "passive"))
      (node (ref "D37") (pin "1") (pinfunction "1_1") (pintype "passive"))
      (node (ref "D45") (pin "1") (pinfunction "1_1") (pintype "passive"))
      (node (ref "D53") (pin "1") (pinfunction "1_1") (pintype "passive"))
      (node (ref "D7") (pin "1") (pinfunction "1_1") (pintype "passive"))
      (node (ref "P3") (pin "7") (pinfunction "7_7") (pintype "passive"))
      (node (ref "U1") (pin "15") (pinfunction "SEG7_15") (pintype "passive"))
    )
    (net (code "34") (name "/SEG8") (class "Default")
      (node (ref "D113") (pin "1") (pinfunction "1_1") (pintype "passive"))
      (node (ref "D114") (pin "1") (pinfunction "1_1") (pintype "passive"))
      (node (ref "D115") (pin "1") (pinfunction "1_1") (pintype "passive"))
      (node (ref "D116") (pin "1") (pinfunction "1_1") (pintype "passive"))
      (node (ref "D22") (pin "1") (pinfunction "1_1") (pintype "passive"))
      (node (ref "D30") (pin "1") (pinfunction "1_1") (pintype "passive"))
      (node (ref "D38") (pin "1") (pinfunction "1_1") (pintype "passive"))
      (node (ref "D46") (pin "1") (pinfunction "1_1") (pintype "passive"))
      (node (ref "D8") (pin "1") (pinfunction "1_1") (pintype "passive"))
      (node (ref "P3") (pin "8") (pinfunction "8_8") (pintype "passive"))
      (node (ref "U1") (pin "16") (pinfunction "SEG8_16") (pintype "passive"))
    )
    (net (code "35") (name "/SWIM") (class "Default")
      (node (ref "P2") (pin "2") (pinfunction "2_2") (pintype "passive"))
      (node (ref "R64") (pin "2") (pinfunction "2_2") (pintype "passive"))
      (node (ref "U4") (pin "18") (pinfunction "PD1(HS)/SWIM_18") (pintype "passive"))
    )
    (net (code "36") (name "/Speed") (class "Default")
      (node (ref "C15") (pin "1") (pinfunction "1_1") (pintype "passive"))
      (node (ref "C8") (pin "1") (pinfunction "1_1") (pintype "passive"))
      (node (ref "R43") (pin "1") (pinfunction "1_1") (pintype "passive"))
      (node (ref "R46") (pin "1") (pinfunction "1_1") (pintype "passive"))
      (node (ref "RW2") (pin "3") (pinfunction "3_3") (pintype "passive"))
      (node (ref "U4") (pin "19") (pinfunction "PD2_(HS)/AIN3/[TIM2_CH3]_19") (pintype "passive"))
    )
    (net (code "37") (name "/Speed_CN") (class "Default")
      (node (ref "P1") (pin "5") (pinfunction "5_5") (pintype "passive"))
      (node (ref "Pad9") (pin "1") (pinfunction "1_1") (pintype "passive"))
      (node (ref "R43") (pin "2") (pinfunction "2_2") (pintype "passive"))
    )
    (net (code "38") (name "/TH1") (class "Default")
      (node (ref "R45") (pin "1") (pinfunction "1_1") (pintype "passive"))
      (node (ref "U4") (pin "2") (pinfunction "UART1_TX/AIN5/(HS)_PD5_2") (pintype "passive"))
    )
    (net (code "39") (name "/右转") (class "Default")
      (node (ref "C22") (pin "1") (pinfunction "1_1") (pintype "passive"))
      (node (ref "R16") (pin "1") (pinfunction "1_1") (pintype "passive"))
      (node (ref "R25") (pin "1") (pinfunction "1_1") (pintype "passive"))
      (node (ref "U4") (pin "12") (pinfunction "PB4_(T)/I2C_SCL_[ADC_ETR]_12") (pintype "passive"))
    )
    (net (code "40") (name "/右转_CN") (class "Default")
      (node (ref "P1") (pin "2") (pinfunction "2_2") (pintype "passive"))
      (node (ref "Pad6") (pin "1") (pinfunction "1_1") (pintype "passive"))
      (node (ref "R16") (pin "2") (pinfunction "2_2") (pintype "passive"))
    )
    (net (code "41") (name "/大灯") (class "Default")
      (node (ref "C9") (pin "1") (pinfunction "1_1") (pintype "passive"))
      (node (ref "R14") (pin "1") (pinfunction "1_1") (pintype "passive"))
      (node (ref "R23") (pin "1") (pinfunction "1_1") (pintype "passive"))
      (node (ref "U4") (pin "13") (pinfunction "PC3_(HS)/TIM1_CH3_[TLI]_[TIM1_CH1N]_13") (pintype "passive"))
    )
    (net (code "42") (name "/大灯_CN") (class "Default")
      (node (ref "P1") (pin "3") (pinfunction "3_3") (pintype "passive"))
      (node (ref "Pad1") (pin "1") (pinfunction "1_1") (pintype "passive"))
      (node (ref "R14") (pin "2") (pinfunction "2_2") (pintype "passive"))
    )
    (net (code "43") (name "/左转") (class "Default")
      (node (ref "C21") (pin "1") (pinfunction "1_1") (pintype "passive"))
      (node (ref "R15") (pin "1") (pinfunction "1_1") (pintype "passive"))
      (node (ref "R24") (pin "1") (pinfunction "1_1") (pintype "passive"))
      (node (ref "U4") (pin "11") (pinfunction "PB5_(T)/I2C_SDA_[TIM1_BKIN]_11") (pintype "passive"))
    )
    (net (code "44") (name "/左转_CN") (class "Default")
      (node (ref "P1") (pin "1") (pinfunction "1_1") (pintype "passive"))
      (node (ref "Pad2") (pin "1") (pinfunction "1_1") (pintype "passive"))
      (node (ref "R15") (pin "2") (pinfunction "2_2") (pintype "passive"))
    )
    (net (code "45") (name "12V") (class "Default")
      (node (ref "P1") (pin "8") (pinfunction "8_8") (pintype "passive"))
    )
    (net (code "46") (name "B+") (class "Default")
      (node (ref "P1") (pin "9") (pinfunction "9_9") (pintype "passive"))
    )
    (net (code "47") (name "GND") (class "Default")
      (node (ref "C10") (pin "2") (pinfunction "2_2") (pintype "passive"))
      (node (ref "C11") (pin "1") (pinfunction "1_1") (pintype "passive"))
      (node (ref "C12") (pin "2") (pinfunction "2_2") (pintype "passive"))
      (node (ref "C13") (pin "1") (pinfunction "1_1") (pintype "passive"))
      (node (ref "C14") (pin "2") (pinfunction "2_2") (pintype "passive"))
      (node (ref "C15") (pin "2") (pinfunction "2_2") (pintype "passive"))
      (node (ref "C16") (pin "1") (pinfunction "1_1") (pintype "passive"))
      (node (ref "C17") (pin "2") (pinfunction "2_2") (pintype "passive"))
      (node (ref "C18") (pin "2") (pinfunction "2_2") (pintype "passive"))
      (node (ref "C19") (pin "1") (pinfunction "1_1") (pintype "passive"))
      (node (ref "C2") (pin "2") (pinfunction "2_2") (pintype "passive"))
      (node (ref "C20") (pin "1") (pinfunction "1_1") (pintype "passive"))
      (node (ref "C21") (pin "2") (pinfunction "2_2") (pintype "passive"))
      (node (ref "C22") (pin "2") (pinfunction "2_2") (pintype "passive"))
      (node (ref "C3") (pin "2") (pinfunction "2_2") (pintype "passive"))
      (node (ref "C4") (pin "2") (pinfunction "2_2") (pintype "passive"))
      (node (ref "C5") (pin "2") (pinfunction "2_2") (pintype "passive"))
      (node (ref "C6") (pin "2") (pinfunction "2_2") (pintype "passive"))
      (node (ref "C7") (pin "2") (pinfunction "2_2") (pintype "passive"))
      (node (ref "C8") (pin "2") (pinfunction "2_2") (pintype "passive"))
      (node (ref "C9") (pin "2") (pinfunction "2_2") (pintype "passive"))
      (node (ref "D14") (pin "1") (pinfunction "1_1") (pintype "passive"))
      (node (ref "P1") (pin "7") (pinfunction "7_7") (pintype "passive"))
      (node (ref "P2") (pin "4") (pinfunction "4_4") (pintype "passive"))
      (node (ref "R21") (pin "2") (pinfunction "2_2") (pintype "passive"))
      (node (ref "R23") (pin "2") (pinfunction "2_2") (pintype "passive"))
      (node (ref "R24") (pin "2") (pinfunction "2_2") (pintype "passive"))
      (node (ref "R25") (pin "2") (pinfunction "2_2") (pintype "passive"))
      (node (ref "R34") (pin "2") (pinfunction "2_2") (pintype "passive"))
      (node (ref "R46") (pin "2") (pinfunction "2_2") (pintype "passive"))
      (node (ref "R47") (pin "2") (pinfunction "2_2") (pintype "passive"))
      (node (ref "R5") (pin "1") (pinfunction "1_1") (pintype "passive"))
      (node (ref "RW2") (pin "1") (pinfunction "1_1") (pintype "passive"))
      (node (ref "TH1") (pin "1") (pinfunction "1_1") (pintype "passive"))
      (node (ref "U1") (pin "6") (pinfunction "VSS_6") (pintype "passive"))
      (node (ref "U3") (pin "1") (pinfunction "GND_1") (pintype "passive"))
      (node (ref "U4") (pin "7") (pinfunction "VSS_7") (pintype "passive"))
    )
    (net (code "48") (name "Net-(C10-Pad1)") (class "Default")
      (node (ref "C10") (pin "1") (pinfunction "1_1") (pintype "passive"))
      (node (ref "R39") (pin "1") (pinfunction "1_1") (pintype "passive"))
      (node (ref "R45") (pin "2") (pinfunction "2_2") (pintype "passive"))
      (node (ref "TH1") (pin "2") (pinfunction "2_2") (pintype "passive"))
    )
    (net (code "49") (name "Net-(C14-Pad1)") (class "Default")
      (node (ref "C14") (pin "1") (pinfunction "1_1") (pintype "passive"))
      (node (ref "R42") (pin "1") (pinfunction "1_1") (pintype "passive"))
      (node (ref "R47") (pin "1") (pinfunction "1_1") (pintype "passive"))
      (node (ref "R51") (pin "2") (pinfunction "2_2") (pintype "passive"))
    )
    (net (code "50") (name "Net-(D1-Pad1)") (class "Default")
      (node (ref "D1") (pin "1") (pinfunction "1_1") (pintype "passive"))
      (node (ref "D15") (pin "1") (pinfunction "1_1") (pintype "passive"))
      (node (ref "D16") (pin "1") (pinfunction "1_1") (pintype "passive"))
      (node (ref "D17") (pin "1") (pinfunction "1_1") (pintype "passive"))
      (node (ref "D18") (pin "1") (pinfunction "1_1") (pintype "passive"))
      (node (ref "D23") (pin "1") (pinfunction "1_1") (pintype "passive"))
      (node (ref "D31") (pin "1") (pinfunction "1_1") (pintype "passive"))
      (node (ref "D39") (pin "1") (pinfunction "1_1") (pintype "passive"))
      (node (ref "D47") (pin "1") (pinfunction "1_1") (pintype "passive"))
      (node (ref "D54") (pin "1") (pinfunction "1_1") (pintype "passive"))
      (node (ref "D55") (pin "1") (pinfunction "1_1") (pintype "passive"))
      (node (ref "D56") (pin "1") (pinfunction "1_1") (pintype "passive"))
      (node (ref "D57") (pin "1") (pinfunction "1_1") (pintype "passive"))
      (node (ref "D58") (pin "1") (pinfunction "1_1") (pintype "passive"))
      (node (ref "D9") (pin "1") (pinfunction "1_1") (pintype "passive"))
    )
    (net (code "51") (name "Net-(D31-Pad2)") (class "Default")
      (node (ref "D31") (pin "2") (pinfunction "2_2") (pintype "passive"))
      (node (ref "D32") (pin "2") (pinfunction "2_2") (pintype "passive"))
      (node (ref "D33") (pin "2") (pinfunction "2_2") (pintype "passive"))
      (node (ref "D34") (pin "2") (pinfunction "2_2") (pintype "passive"))
      (node (ref "D35") (pin "2") (pinfunction "2_2") (pintype "passive"))
      (node (ref "D36") (pin "2") (pinfunction "2_2") (pintype "passive"))
      (node (ref "D37") (pin "2") (pinfunction "2_2") (pintype "passive"))
      (node (ref "D38") (pin "2") (pinfunction "2_2") (pintype "passive"))
    )
    (net (code "52") (name "Net-(R3-Pad2)") (class "Default")
      (node (ref "R3") (pin "2") (pinfunction "2_2") (pintype "passive"))
      (node (ref "R4") (pin "1") (pinfunction "1_1") (pintype "passive"))
      (node (ref "R5") (pin "2") (pinfunction "2_2") (pintype "passive"))
    )
    (net (code "53") (name "Net-(U3-BST)") (class "Default")
      (node (ref "C1") (pin "2") (pinfunction "2_2") (pintype "passive"))
      (node (ref "U3") (pin "6") (pinfunction "BST_6") (pintype "passive"))
    )
    (net (code "54") (name "Net-(U3-EN)") (class "Default")
      (node (ref "R2") (pin "2") (pinfunction "2_2") (pintype "passive"))
      (node (ref "U3") (pin "5") (pinfunction "EN_5") (pintype "passive"))
    )
    (net (code "55") (name "Net-(U3-FB)") (class "Default")
      (node (ref "R4") (pin "2") (pinfunction "2_2") (pintype "passive"))
      (node (ref "U3") (pin "4") (pinfunction "FB_4") (pintype "passive"))
    )
    (net (code "56") (name "Net-(U3-SW)") (class "Default")
      (node (ref "C1") (pin "1") (pinfunction "1_1") (pintype "passive"))
      (node (ref "L1") (pin "1") (pinfunction "1_1") (pintype "passive"))
      (node (ref "U3") (pin "2") (pinfunction "SW_2") (pintype "passive"))
    )
    (net (code "57") (name "Net-(U4-VCAP)") (class "Default")
      (node (ref "C17") (pin "1") (pinfunction "1_1") (pintype "passive"))
      (node (ref "U4") (pin "8") (pinfunction "VCAP_8") (pintype "passive"))
    )
    (net (code "58") (name "unconnected-(RW2-Pad2)") (class "Default")
      (node (ref "RW2") (pin "2") (pinfunction "2_2") (pintype "passive"))
    )
    (net (code "59") (name "unconnected-(U1-GRID15-Pad4)") (class "Default")
      (node (ref "U1") (pin "4") (pinfunction "GRID15_4") (pintype "passive"))
    )
    (net (code "60") (name "unconnected-(U1-GRID16-Pad5)") (class "Default")
      (node (ref "U1") (pin "5") (pinfunction "GRID16_5") (pintype "passive"))
    )
    (net (code "61") (name "unconnected-(U1-SEG1-Pad9)") (class "Default")
      (node (ref "U1") (pin "9") (pinfunction "SEG1_9") (pintype "passive"))
    )
    (net (code "62") (name "unconnected-(U4-OSCIN{slash}PA1-Pad5)") (class "Default")
      (node (ref "U4") (pin "5") (pinfunction "OSCIN/PA1_5") (pintype "passive"))
    )
    (net (code "63") (name "unconnected-(U4-OSCOUT{slash}PA2-Pad6)") (class "Default")
      (node (ref "U4") (pin "6") (pinfunction "OSCOUT/PA2_6") (pintype "passive"))
    )
    (net (code "64") (name "unconnected-(U4-PC4_(HS){slash}TIM1_CH4{slash}CLK_CCO{slash}AIN2{slash}[TIM1_CH2N]-Pad14)") (class "Default")
      (node (ref "U4") (pin "14") (pinfunction "PC4_(HS)/TIM1_CH4/CLK_CCO/AIN2/[TIM1_CH2N]_14") (pintype "passive"))
    )
    (net (code "65") (name "unconnected-(U4-PC7_(HS){slash}SPI_MISO_[TIM1_CH2]-Pad17)") (class "Default")
      (node (ref "U4") (pin "17") (pinfunction "PC7_(HS)/SPI_MISO_[TIM1_CH2]_17") (pintype "passive"))
    )
    (net (code "66") (name "unconnected-(U4-[SPI_NSS]_TIM2_CH3{slash}(HS)_PA3-Pad10)") (class "Default")
      (node (ref "U4") (pin "10") (pinfunction "[SPI_NSS]_TIM2_CH3/(HS)_PA3_10") (pintype "passive"))
    )
  )
)
